# EAT0001.net
KiCad netlist of a schematic drawn in EAGLE
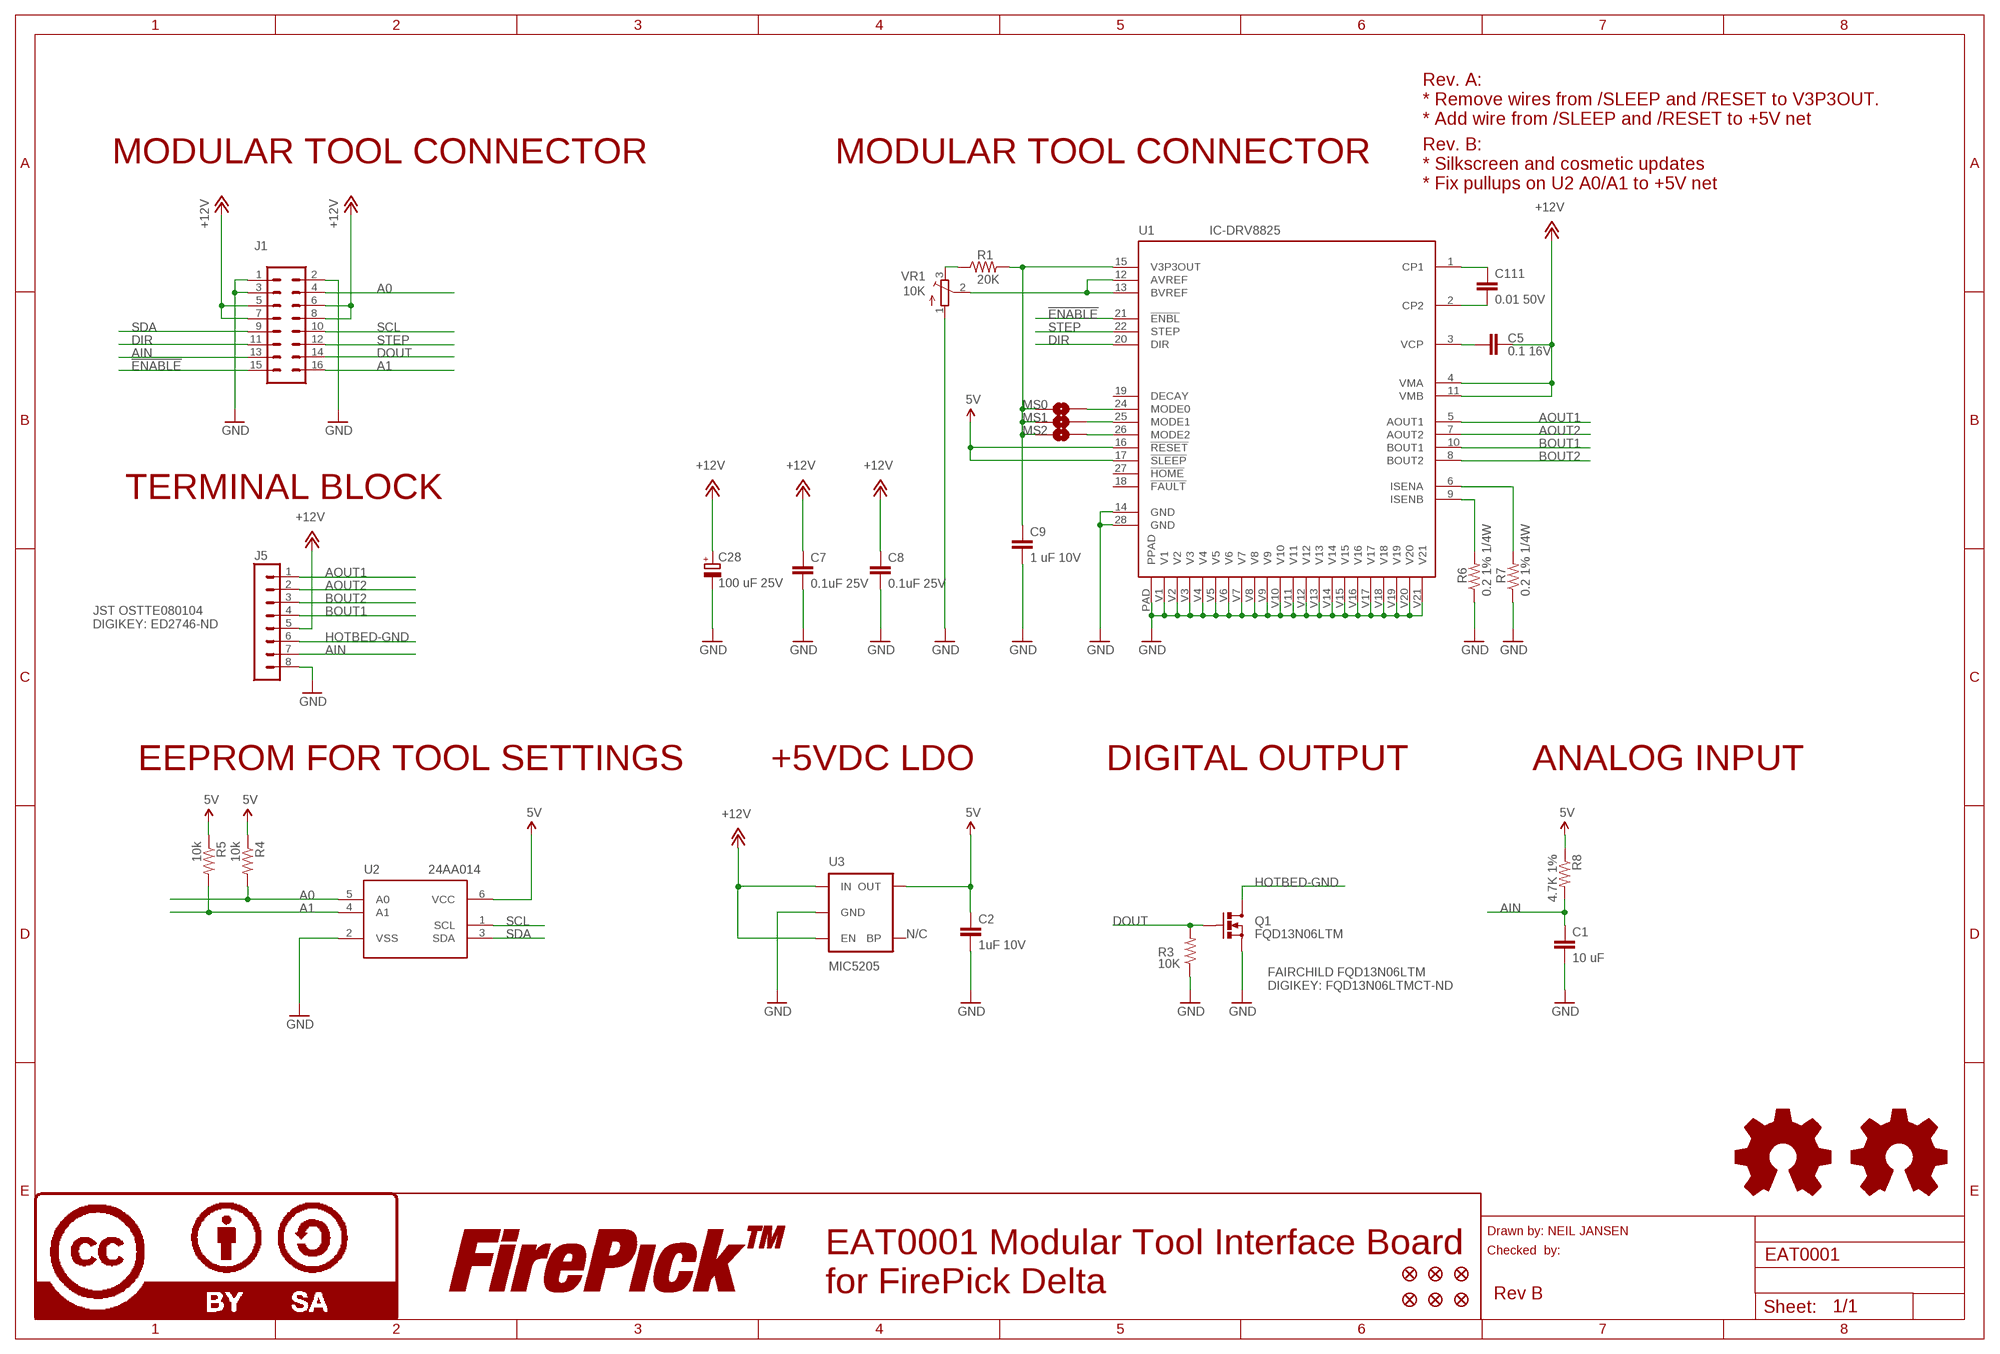
[diagram p0: schematic, sheet 1]

(export (version "E")
  (design (tool "Eeschema 10.0.6"))
  (components
    (comp (ref "C1")
      (value "10 uF")
      (footprint "eagle-import:0805")
      (libsource (lib "eagle-import") (part "CAP0805"))
    )
    (comp (ref "C2")
      (value "1uF 10V")
      (footprint "eagle-import:0805")
      (libsource (lib "eagle-import") (part "CAP0805"))
    )
    (comp (ref "C5")
      (value "0.1 16V")
      (footprint "eagle-import:0805")
      (libsource (lib "eagle-import") (part "CAP0805"))
    )
    (comp (ref "C7")
      (value "0.1uF 25V")
      (footprint "eagle-import:0805")
      (libsource (lib "eagle-import") (part "CAP0805"))
    )
    (comp (ref "C8")
      (value "0.1uF 25V")
      (footprint "eagle-import:0805")
      (libsource (lib "eagle-import") (part "CAP0805"))
    )
    (comp (ref "C9")
      (value "1 uF 10V")
      (footprint "eagle-import:0805")
      (libsource (lib "eagle-import") (part "CAP0805"))
    )
    (comp (ref "C28")
      (value "100 uF 25V")
      (footprint "eagle-import:UD-6,3X7,7_NICHICON")
      (libsource (lib "eagle-import") (part "CPOL-EUUD-6,3X7,7"))
    )
    (comp (ref "C111")
      (value "0.01 50V")
      (footprint "eagle-import:0805")
      (libsource (lib "eagle-import") (part "CAP0805"))
    )
    (comp (ref "FID1")
      (value "FIDUCIAL1X2")
      (footprint "eagle-import:FIDUCIAL-1X2")
      (libsource (lib "eagle-import") (part "FIDUCIAL1X2"))
    )
    (comp (ref "FID2")
      (value "FIDUCIAL1X2")
      (footprint "eagle-import:FIDUCIAL-1X2")
      (libsource (lib "eagle-import") (part "FIDUCIAL1X2"))
    )
    (comp (ref "FID3")
      (value "FIDUCIAL1X2")
      (footprint "eagle-import:FIDUCIAL-1X2")
      (libsource (lib "eagle-import") (part "FIDUCIAL1X2"))
    )
    (comp (ref "FID4")
      (value "FIDUCIAL1X2")
      (footprint "eagle-import:FIDUCIAL-1X2")
      (libsource (lib "eagle-import") (part "FIDUCIAL1X2"))
    )
    (comp (ref "FID5")
      (value "FIDUCIAL1X2")
      (footprint "eagle-import:FIDUCIAL-1X2")
      (libsource (lib "eagle-import") (part "FIDUCIAL1X2"))
    )
    (comp (ref "FID6")
      (value "FIDUCIAL1X2")
      (footprint "eagle-import:FIDUCIAL-1X2")
      (libsource (lib "eagle-import") (part "FIDUCIAL1X2"))
    )
    (comp (ref "J1")
      (value "CONN-RECT-16PIN-2ROWSIDE")
      (footprint "eagle-import:CONN-RECT-2.54MM-16PIN-2ROW-SIDE")
      (libsource (lib "eagle-import") (part "CONN-RECT-16PIN-2ROWSIDE"))
    )
    (comp (ref "J5")
      (value "CONN-OSTTE1201X4")
      (footprint "eagle-import:CONN-OSTTE1201X4")
      (libsource (lib "eagle-import") (part "CONN-OSTTE1201X4"))
    )
    (comp (ref "LOGO1")
      (value "LOGO-OSHWSMALL")
      (footprint "eagle-import:LOGO-OSHW-SMALL")
      (libsource (lib "eagle-import") (part "LOGO-OSHWSMALL"))
    )
    (comp (ref "LOGO4")
      (value "LOGO-FIREPICKMEDIUM")
      (footprint "eagle-import:LOGO-FIREPICK-MEDIUM")
      (libsource (lib "eagle-import") (part "LOGO-FIREPICKMEDIUM"))
    )
    (comp (ref "LOGO5")
      (value "LOGO-OSHWSMALL")
      (footprint "eagle-import:LOGO-OSHW-SMALL")
      (libsource (lib "eagle-import") (part "LOGO-OSHWSMALL"))
    )
    (comp (ref "LOGO6")
      (value "LOGO-CC-BY-SAMEDIUM")
      (footprint "eagle-import:LOGO-CC-BY-SA-MEDIUM")
      (libsource (lib "eagle-import") (part "LOGO-CC-BY-SAMEDIUM"))
    )
    (comp (ref "MS0")
      (value "JUMPER")
      (footprint "eagle-import:JUMPER-NC")
      (libsource (lib "eagle-import") (part "JUMPER"))
    )
    (comp (ref "MS1")
      (value "JUMPER")
      (footprint "eagle-import:JUMPER-NC")
      (libsource (lib "eagle-import") (part "JUMPER"))
    )
    (comp (ref "MS2")
      (value "JUMPER")
      (footprint "eagle-import:JUMPER-NC")
      (libsource (lib "eagle-import") (part "JUMPER"))
    )
    (comp (ref "Q1")
      (value "FQD13N06LTM")
      (footprint "eagle-import:DPAK")
      (libsource (lib "eagle-import") (part "MOSFET-NCHANNELFDD8580"))
    )
    (comp (ref "R1")
      (value "20K")
      (footprint "eagle-import:0805")
      (libsource (lib "eagle-import") (part "RESISTOR0805-RES"))
    )
    (comp (ref "R3")
      (value "10K")
      (footprint "eagle-import:0805")
      (libsource (lib "eagle-import") (part "RESISTOR0805-RES"))
    )
    (comp (ref "R4")
      (value "10k")
      (footprint "eagle-import:0805")
      (libsource (lib "eagle-import") (part "RESISTOR0805-RES"))
    )
    (comp (ref "R5")
      (value "10k")
      (footprint "eagle-import:0805")
      (libsource (lib "eagle-import") (part "RESISTOR0805-RES"))
    )
    (comp (ref "R6")
      (value "0.2 1% 1/4W")
      (footprint "eagle-import:0805")
      (libsource (lib "eagle-import") (part "RESISTOR0805-RES"))
    )
    (comp (ref "R7")
      (value "0.2 1% 1/4W")
      (footprint "eagle-import:0805")
      (libsource (lib "eagle-import") (part "RESISTOR0805-RES"))
    )
    (comp (ref "R8")
      (value "4.7K 1%")
      (footprint "eagle-import:0805")
      (libsource (lib "eagle-import") (part "RESISTOR0805-RES"))
    )
    (comp (ref "U1")
      (value "IC-DRV8825")
      (footprint "eagle-import:TSSOP28_PAD")
      (libsource (lib "eagle-import") (part "IC-DRV8825"))
    )
    (comp (ref "U2")
      (value "24AA014")
      (footprint "eagle-import:SOT23-6")
      (libsource (lib "eagle-import") (part "IC-24AA014"))
    )
    (comp (ref "U3")
      (value "MIC5205")
      (footprint "eagle-import:SOT23-5")
      (libsource (lib "eagle-import") (part "MIC52055V"))
    )
    (comp (ref "VR1")
      (value "10K")
      (footprint "eagle-import:TC33X")
      (libsource (lib "eagle-import") (part "TRIMPOTTC33X"))
    )
  )
  (nets
    (net (code "1") (name "+12V") (class "Default")
      (node (ref "C28") (pin "+") (pinfunction "+_+") (pintype "passive"))
      (node (ref "C5") (pin "1") (pinfunction "1_1") (pintype "passive"))
      (node (ref "C7") (pin "1") (pinfunction "1_1") (pintype "passive"))
      (node (ref "C8") (pin "1") (pinfunction "1_1") (pintype "passive"))
      (node (ref "J1") (pin "5") (pinfunction "5_5") (pintype "passive"))
      (node (ref "J1") (pin "6") (pinfunction "6_6") (pintype "passive"))
      (node (ref "J1") (pin "7") (pinfunction "7_7") (pintype "passive"))
      (node (ref "J1") (pin "8") (pinfunction "8_8") (pintype "passive"))
      (node (ref "J5") (pin "5") (pinfunction "5_5") (pintype "passive"))
      (node (ref "U1") (pin "11") (pinfunction "VMB_11") (pintype "bidirectional"))
      (node (ref "U1") (pin "4") (pinfunction "VMA_4") (pintype "bidirectional"))
      (node (ref "U3") (pin "1") (pinfunction "IN_1") (pintype "input"))
      (node (ref "U3") (pin "3") (pinfunction "EN_3") (pintype "input"))
    )
    (net (code "2") (name "/A0") (class "Default")
      (node (ref "J1") (pin "4") (pinfunction "4_4") (pintype "passive"))
      (node (ref "R4") (pin "2") (pinfunction "2_2") (pintype "passive"))
      (node (ref "U2") (pin "5") (pinfunction "A0_5") (pintype "bidirectional"))
    )
    (net (code "3") (name "/A1") (class "Default")
      (node (ref "J1") (pin "16") (pinfunction "16_16") (pintype "passive"))
      (node (ref "R5") (pin "2") (pinfunction "2_2") (pintype "passive"))
      (node (ref "U2") (pin "4") (pinfunction "A1_4") (pintype "bidirectional"))
    )
    (net (code "4") (name "/AIN") (class "Default")
      (node (ref "C1") (pin "1") (pinfunction "1_1") (pintype "passive"))
      (node (ref "J1") (pin "13") (pinfunction "13_13") (pintype "passive"))
      (node (ref "J5") (pin "7") (pinfunction "7_7") (pintype "passive"))
      (node (ref "R8") (pin "2") (pinfunction "2_2") (pintype "passive"))
    )
    (net (code "5") (name "/AOUT1") (class "Default")
      (node (ref "J5") (pin "1") (pinfunction "1_1") (pintype "passive"))
      (node (ref "U1") (pin "5") (pinfunction "AOUT1_5") (pintype "bidirectional"))
    )
    (net (code "6") (name "/AOUT2") (class "Default")
      (node (ref "J5") (pin "2") (pinfunction "2_2") (pintype "passive"))
      (node (ref "U1") (pin "7") (pinfunction "AOUT2_7") (pintype "bidirectional"))
    )
    (net (code "7") (name "/BOUT1") (class "Default")
      (node (ref "J5") (pin "4") (pinfunction "4_4") (pintype "passive"))
      (node (ref "U1") (pin "10") (pinfunction "BOUT1_10") (pintype "bidirectional"))
    )
    (net (code "8") (name "/BOUT2") (class "Default")
      (node (ref "J5") (pin "3") (pinfunction "3_3") (pintype "passive"))
      (node (ref "U1") (pin "8") (pinfunction "BOUT2_8") (pintype "bidirectional"))
    )
    (net (code "9") (name "/DIR") (class "Default")
      (node (ref "J1") (pin "11") (pinfunction "11_11") (pintype "passive"))
      (node (ref "U1") (pin "20") (pinfunction "DIR_20") (pintype "bidirectional"))
    )
    (net (code "10") (name "/DOUT") (class "Default")
      (node (ref "J1") (pin "14") (pinfunction "14_14") (pintype "passive"))
      (node (ref "Q1") (pin "1") (pinfunction "G_1") (pintype "passive"))
      (node (ref "R3") (pin "2") (pinfunction "2_2") (pintype "passive"))
    )
    (net (code "11") (name "/HOTBED-GND") (class "Default")
      (node (ref "J5") (pin "6") (pinfunction "6_6") (pintype "passive"))
      (node (ref "Q1") (pin "4") (pinfunction "D_4") (pintype "passive"))
    )
    (net (code "12") (name "/SCL") (class "Default")
      (node (ref "J1") (pin "10") (pinfunction "10_10") (pintype "passive"))
      (node (ref "U2") (pin "1") (pinfunction "SCL_1") (pintype "bidirectional"))
    )
    (net (code "13") (name "/SDA") (class "Default")
      (node (ref "J1") (pin "9") (pinfunction "9_9") (pintype "passive"))
      (node (ref "U2") (pin "3") (pinfunction "SDA_3") (pintype "bidirectional"))
    )
    (net (code "14") (name "/STEP") (class "Default")
      (node (ref "J1") (pin "12") (pinfunction "12_12") (pintype "passive"))
      (node (ref "U1") (pin "22") (pinfunction "STEP_22") (pintype "bidirectional"))
    )
    (net (code "15") (name "/~{ENABLE}") (class "Default")
      (node (ref "J1") (pin "15") (pinfunction "15_15") (pintype "passive"))
      (node (ref "U1") (pin "21") (pinfunction "~{ENBL}_21") (pintype "bidirectional"))
    )
    (net (code "16") (name "5V") (class "Default")
      (node (ref "C2") (pin "1") (pinfunction "1_1") (pintype "passive"))
      (node (ref "R4") (pin "1") (pinfunction "1_1") (pintype "passive"))
      (node (ref "R5") (pin "1") (pinfunction "1_1") (pintype "passive"))
      (node (ref "R8") (pin "1") (pinfunction "1_1") (pintype "passive"))
      (node (ref "U1") (pin "16") (pinfunction "~{RESET}_16") (pintype "bidirectional"))
      (node (ref "U1") (pin "17") (pinfunction "~{SLEEP}_17") (pintype "bidirectional"))
      (node (ref "U2") (pin "6") (pinfunction "VCC_6") (pintype "bidirectional"))
      (node (ref "U3") (pin "5") (pinfunction "OUT_5") (pintype "passive"))
    )
    (net (code "17") (name "GND") (class "Default")
      (node (ref "C1") (pin "2") (pinfunction "2_2") (pintype "passive"))
      (node (ref "C2") (pin "2") (pinfunction "2_2") (pintype "passive"))
      (node (ref "C28") (pin "-") (pinfunction "-_-") (pintype "passive"))
      (node (ref "C7") (pin "2") (pinfunction "2_2") (pintype "passive"))
      (node (ref "C8") (pin "2") (pinfunction "2_2") (pintype "passive"))
      (node (ref "C9") (pin "2") (pinfunction "2_2") (pintype "passive"))
      (node (ref "J1") (pin "1") (pinfunction "1_1") (pintype "passive"))
      (node (ref "J1") (pin "2") (pinfunction "2_2") (pintype "passive"))
      (node (ref "J1") (pin "3") (pinfunction "3_3") (pintype "passive"))
      (node (ref "J5") (pin "8") (pinfunction "8_8") (pintype "passive"))
      (node (ref "Q1") (pin "3") (pinfunction "S_3") (pintype "passive"))
      (node (ref "R3") (pin "1") (pinfunction "1_1") (pintype "passive"))
      (node (ref "R6") (pin "1") (pinfunction "1_1") (pintype "passive"))
      (node (ref "R7") (pin "1") (pinfunction "1_1") (pintype "passive"))
      (node (ref "U1") (pin "14") (pinfunction "GND_14") (pintype "bidirectional"))
      (node (ref "U1") (pin "28") (pinfunction "GND_28") (pintype "bidirectional"))
      (node (ref "U1") (pin "PAD") (pinfunction "PPAD_PAD") (pintype "bidirectional"))
      (node (ref "U1") (pin "V1") (pinfunction "V1_V1") (pintype "bidirectional"))
      (node (ref "U1") (pin "V10") (pinfunction "V10_V10") (pintype "bidirectional"))
      (node (ref "U1") (pin "V11") (pinfunction "V11_V11") (pintype "bidirectional"))
      (node (ref "U1") (pin "V12") (pinfunction "V12_V12") (pintype "bidirectional"))
      (node (ref "U1") (pin "V13") (pinfunction "V13_V13") (pintype "bidirectional"))
      (node (ref "U1") (pin "V14") (pinfunction "V14_V14") (pintype "bidirectional"))
      (node (ref "U1") (pin "V15") (pinfunction "V15_V15") (pintype "bidirectional"))
      (node (ref "U1") (pin "V16") (pinfunction "V16_V16") (pintype "bidirectional"))
      (node (ref "U1") (pin "V17") (pinfunction "V17_V17") (pintype "bidirectional"))
      (node (ref "U1") (pin "V18") (pinfunction "V18_V18") (pintype "bidirectional"))
      (node (ref "U1") (pin "V19") (pinfunction "V19_V19") (pintype "bidirectional"))
      (node (ref "U1") (pin "V2") (pinfunction "V2_V2") (pintype "bidirectional"))
      (node (ref "U1") (pin "V20") (pinfunction "V20_V20") (pintype "bidirectional"))
      (node (ref "U1") (pin "V21") (pinfunction "V21_V21") (pintype "bidirectional"))
      (node (ref "U1") (pin "V3") (pinfunction "V3_V3") (pintype "bidirectional"))
      (node (ref "U1") (pin "V4") (pinfunction "V4_V4") (pintype "bidirectional"))
      (node (ref "U1") (pin "V5") (pinfunction "V5_V5") (pintype "bidirectional"))
      (node (ref "U1") (pin "V6") (pinfunction "V6_V6") (pintype "bidirectional"))
      (node (ref "U1") (pin "V7") (pinfunction "V7_V7") (pintype "bidirectional"))
      (node (ref "U1") (pin "V8") (pinfunction "V8_V8") (pintype "bidirectional"))
      (node (ref "U1") (pin "V9") (pinfunction "V9_V9") (pintype "bidirectional"))
      (node (ref "U2") (pin "2") (pinfunction "VSS_2") (pintype "bidirectional"))
      (node (ref "U3") (pin "2") (pinfunction "GND_2") (pintype "input"))
      (node (ref "VR1") (pin "1") (pinfunction "A_1") (pintype "passive"))
    )
    (net (code "18") (name "Net-(U1-AVREF)") (class "Default")
      (node (ref "U1") (pin "12") (pinfunction "AVREF_12") (pintype "bidirectional"))
      (node (ref "U1") (pin "13") (pinfunction "BVREF_13") (pintype "bidirectional"))
      (node (ref "VR1") (pin "2") (pinfunction "S_2") (pintype "passive"))
    )
    (net (code "19") (name "Net-(U1-CP1)") (class "Default")
      (node (ref "C111") (pin "1") (pinfunction "1_1") (pintype "passive"))
      (node (ref "U1") (pin "1") (pinfunction "CP1_1") (pintype "bidirectional"))
    )
    (net (code "20") (name "Net-(U1-CP2)") (class "Default")
      (node (ref "C111") (pin "2") (pinfunction "2_2") (pintype "passive"))
      (node (ref "U1") (pin "2") (pinfunction "CP2_2") (pintype "bidirectional"))
    )
    (net (code "21") (name "Net-(U1-ISENA)") (class "Default")
      (node (ref "R7") (pin "2") (pinfunction "2_2") (pintype "passive"))
      (node (ref "U1") (pin "6") (pinfunction "ISENA_6") (pintype "bidirectional"))
    )
    (net (code "22") (name "Net-(U1-ISENB)") (class "Default")
      (node (ref "R6") (pin "2") (pinfunction "2_2") (pintype "passive"))
      (node (ref "U1") (pin "9") (pinfunction "ISENB_9") (pintype "bidirectional"))
    )
    (net (code "23") (name "Net-(U1-MODE0)") (class "Default")
      (node (ref "MS0") (pin "2") (pinfunction "2_2") (pintype "passive"))
      (node (ref "U1") (pin "24") (pinfunction "MODE0_24") (pintype "bidirectional"))
    )
    (net (code "24") (name "Net-(U1-MODE1)") (class "Default")
      (node (ref "MS1") (pin "2") (pinfunction "2_2") (pintype "passive"))
      (node (ref "U1") (pin "25") (pinfunction "MODE1_25") (pintype "bidirectional"))
    )
    (net (code "25") (name "Net-(U1-MODE2)") (class "Default")
      (node (ref "MS2") (pin "2") (pinfunction "2_2") (pintype "passive"))
      (node (ref "U1") (pin "26") (pinfunction "MODE2_26") (pintype "bidirectional"))
    )
    (net (code "26") (name "Net-(U1-V3P3OUT)") (class "Default")
      (node (ref "C9") (pin "1") (pinfunction "1_1") (pintype "passive"))
      (node (ref "MS0") (pin "1") (pinfunction "1_1") (pintype "passive"))
      (node (ref "MS1") (pin "1") (pinfunction "1_1") (pintype "passive"))
      (node (ref "MS2") (pin "1") (pinfunction "1_1") (pintype "passive"))
      (node (ref "R1") (pin "2") (pinfunction "2_2") (pintype "passive"))
      (node (ref "U1") (pin "15") (pinfunction "V3P3OUT_15") (pintype "bidirectional"))
    )
    (net (code "27") (name "Net-(U1-VCP)") (class "Default")
      (node (ref "C5") (pin "2") (pinfunction "2_2") (pintype "passive"))
      (node (ref "U1") (pin "3") (pinfunction "VCP_3") (pintype "bidirectional"))
    )
    (net (code "28") (name "Net-(VR1-E)") (class "Default")
      (node (ref "R1") (pin "1") (pinfunction "1_1") (pintype "passive"))
      (node (ref "VR1") (pin "3") (pinfunction "E_3") (pintype "passive"))
    )
    (net (code "29") (name "unconnected-(U1-DECAY-Pad19)") (class "Default")
      (node (ref "U1") (pin "19") (pinfunction "DECAY_19") (pintype "bidirectional"))
    )
    (net (code "30") (name "unconnected-(U1-~{FAULT}-Pad18)") (class "Default")
      (node (ref "U1") (pin "18") (pinfunction "~{FAULT}_18") (pintype "bidirectional"))
    )
    (net (code "31") (name "unconnected-(U1-~{HOME}-Pad27)") (class "Default")
      (node (ref "U1") (pin "27") (pinfunction "~{HOME}_27") (pintype "bidirectional"))
    )
    (net (code "32") (name "unconnected-(U3-BP-Pad4)") (class "Default")
      (node (ref "U3") (pin "4") (pinfunction "BP_4") (pintype "input"))
    )
  )
)
